# 0_3.net
KiCad netlist of a schematic drawn in Altium Designer
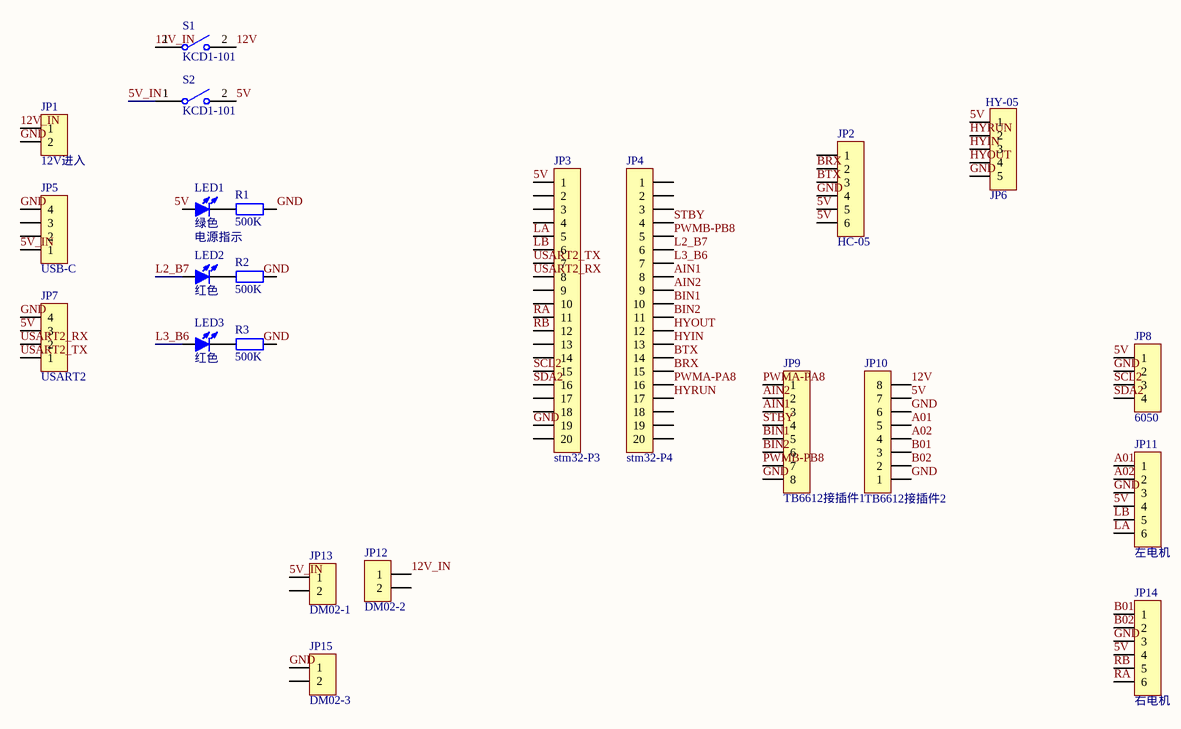
[diagram p0: 0.3.SchDoc]

(export (version "E")
  (design (tool "Eeschema 10.0.6"))
  (components
    (comp (ref "JP1")
      (value "HDR-1X2")
      (footprint "KF2EDGK5.08-LI-2P")
      (description "2P接插件")
      (fields (field (name "BOM名称") "12V进入") (field (name "版权归属") "源创客"))
      (libsource (lib "5.8 - 接插件-脚距5.08 (200mil) ") (part "Header 2"))
    )
    (comp (ref "JP2")
      (value "HC-05")
      (footprint "HDR2.54-M-LI-6P")
      (description "6P接插件")
      (fields (field (name "BOM名称") "HC-05") (field (name "版权归属") "封装库来自淘宝 ID：黄晶宝石"))
      (libsource (lib "5.3 - 接插件-脚距2.54 (100mil) ") (part "Header 6"))
    )
    (comp (ref "JP3")
      (value "HDR-1X20")
      (footprint "HDR2.54-M-LI-20P")
      (description "20P接插件")
      (fields (field (name "BOM名称") "stm32-P3") (field (name "版权归属") "封装库来自淘宝 ID：黄晶宝石"))
      (libsource (lib "5.3 - 接插件-脚距2.54 (100mil) ") (part "Header 20"))
    )
    (comp (ref "JP4")
      (value "HDR-1X20")
      (footprint "HDR2.54-M-LI-20P")
      (description "20P接插件")
      (fields (field (name "BOM名称") "stm32-P4") (field (name "版权归属") "封装库来自淘宝 ID：黄晶宝石"))
      (libsource (lib "") (part "Header 20_1"))
    )
    (comp (ref "JP5")
      (value "HDR-1X4")
      (footprint "HDR2.54-M-LI-4P")
      (description "4P接插件")
      (fields (field (name "BOM名称") "USB-C") (field (name "版权归属") "封装库来自淘宝 ID：黄晶宝石"))
      (libsource (lib "5.3 - 接插件-脚距2.54 (100mil) ") (part "Header 4"))
    )
    (comp (ref "JP6")
      (value "HY-05")
      (footprint "HDR2.54-M-LI-5P")
      (description "5P接插件")
      (fields (field (name "版权归属") "封装库来自淘宝 ID：黄晶宝石"))
      (libsource (lib "5.3 - 接插件-脚距2.54 (100mil) ") (part "Header 5"))
    )
    (comp (ref "JP7")
      (value "HDR-1X4")
      (footprint "HDR2.54-M-LI-4P")
      (description "4P接插件")
      (fields (field (name "BOM名称") "USART2") (field (name "版权归属") "封装库来自淘宝 ID：黄晶宝石"))
      (libsource (lib "5.3 - 接插件-脚距2.54 (100mil) ") (part "Header 4"))
    )
    (comp (ref "JP8")
      (value "HDR-1X4")
      (footprint "HDR2.54-M-LI-4P")
      (description "4P接插件")
      (fields (field (name "BOM名称") "6050") (field (name "版权归属") "封装库来自淘宝 ID：黄晶宝石"))
      (libsource (lib "") (part "Header 4_1"))
    )
    (comp (ref "JP9")
      (value "HDR-1X8")
      (footprint "HDR2.54-M-LI-8P")
      (description "8P接插件")
      (fields (field (name "BOM名称") "TB6612接插件1") (field (name "版权归属") "封装库来自淘宝 ID：黄晶宝石"))
      (libsource (lib "5.3 - 接插件-脚距2.54 (100mil) ") (part "Header 8"))
    )
    (comp (ref "JP10")
      (value "HDR-1X8")
      (footprint "HDR2.54-M-LI-8P")
      (description "8P接插件")
      (fields (field (name "BOM名称") "TB6612接插件2") (field (name "版权归属") "封装库来自淘宝 ID：黄晶宝石"))
      (libsource (lib "") (part "Header 8_1"))
    )
    (comp (ref "JP11")
      (value "HDR-1X6")
      (footprint "KF128-5.08-6P")
      (description "6P接插件")
      (fields (field (name "BOM名称") "左电机") (field (name "版权归属") "源创客"))
      (libsource (lib "5.8 - 接插件-脚距5.08 (200mil) ") (part "Header 6"))
    )
    (comp (ref "JP12")
      (value "HDR-1X2")
      (footprint "HDR2.54-M-LI-2P")
      (description "2P接插件")
      (fields (field (name "BOM名称") "DM02-2") (field (name "版权归属") "封装库来自淘宝 ID：黄晶宝石"))
      (libsource (lib "") (part "Header 2_1"))
    )
    (comp (ref "JP13")
      (value "HDR-1X2")
      (footprint "HDR2.54-M-LI-2P")
      (description "2P接插件")
      (fields (field (name "BOM名称") "DM02-1") (field (name "版权归属") "封装库来自淘宝 ID：黄晶宝石"))
      (libsource (lib "5.3 - 接插件-脚距2.54 (100mil) ") (part "Header 2"))
    )
    (comp (ref "JP14")
      (value "HDR-1X6")
      (footprint "KF128-5.08-6P")
      (description "6P接插件")
      (fields (field (name "BOM名称") "右电机") (field (name "版权归属") "源创客"))
      (libsource (lib "5.8 - 接插件-脚距5.08 (200mil) ") (part "Header 6"))
    )
    (comp (ref "JP15")
      (value "HDR-1X2")
      (footprint "HDR2.54-M-LI-2P")
      (description "2P接插件")
      (fields (field (name "BOM名称") "DM02-3") (field (name "版权归属") "封装库来自淘宝 ID：黄晶宝石"))
      (libsource (lib "5.3 - 接插件-脚距2.54 (100mil) ") (part "Header 2"))
    )
    (comp (ref "LED1")
      (value "绿色")
      (footprint "LED 0805G")
      (description "贴片LED")
      (fields (field (name "BOM名称") "电源指示") (field (name "版权归属") "源创客"))
      (libsource (lib "LED") (part "LED-SMD"))
    )
    (comp (ref "LED2")
      (value "红色")
      (footprint "LED 0805G")
      (description "贴片LED")
      (fields (field (name "版权归属") "源创客"))
      (libsource (lib "LED") (part "LED-SMD"))
    )
    (comp (ref "LED3")
      (value "红色")
      (footprint "LED 0805G")
      (description "贴片LED")
      (fields (field (name "版权归属") "源创客"))
      (libsource (lib "LED") (part "LED-SMD"))
    )
    (comp (ref "R1")
      (value "500K")
      (footprint "R 0805_M")
      (description "贴片电阻")
      (fields (field (name "版权归属") "来自淘宝 ID：黄晶宝石"))
      (libsource (lib "0.1 - 电阻-电容-电感") (part "R"))
    )
    (comp (ref "R2")
      (value "500K")
      (footprint "R 0805_M")
      (description "贴片电阻")
      (fields (field (name "版权归属") "来自淘宝 ID：黄晶宝石"))
      (libsource (lib "0.1 - 电阻-电容-电感") (part "R"))
    )
    (comp (ref "R3")
      (value "500K")
      (footprint "R 0805_M")
      (description "贴片电阻")
      (fields (field (name "版权归属") "来自淘宝 ID：黄晶宝石"))
      (libsource (lib "0.1 - 电阻-电容-电感") (part "R"))
    )
    (comp (ref "S1")
      (value "KCD1-101")
      (footprint "KCD1-101")
      (description "1路单刀船型开关")
      (fields (field (name "版权归属") "封装库来自淘宝 ID：黄晶宝石"))
      (libsource (lib "0.7 - 常用按键-开关") (part "KCD1-101"))
    )
    (comp (ref "S2")
      (value "KCD1-101")
      (footprint "KCD1-101")
      (description "1路单刀船型开关")
      (fields (field (name "版权归属") "封装库来自淘宝 ID：黄晶宝石"))
      (libsource (lib "0.7 - 常用按键-开关") (part "KCD1-101"))
    )
  )
  (nets
    (net (code "1") (name "/5V") (class "Default")
      (node (ref "JP10") (pin "7") (pinfunction "7_7") (pintype "passive"))
      (node (ref "JP11") (pin "4") (pinfunction "4_4") (pintype "passive"))
      (node (ref "JP14") (pin "4") (pinfunction "4_4") (pintype "passive"))
      (node (ref "JP2") (pin "5") (pinfunction "5_5") (pintype "passive"))
      (node (ref "JP2") (pin "6") (pinfunction "6_6") (pintype "passive"))
      (node (ref "JP3") (pin "1") (pinfunction "1_1") (pintype "passive"))
      (node (ref "JP6") (pin "1") (pinfunction "1_1") (pintype "passive"))
      (node (ref "JP7") (pin "3") (pinfunction "3_3") (pintype "passive"))
      (node (ref "JP8") (pin "1") (pinfunction "1_1") (pintype "passive"))
      (node (ref "LED1") (pin "1") (pinfunction "A_1") (pintype "passive"))
      (node (ref "S2") (pin "2") (pinfunction "2_2") (pintype "passive"))
    )
    (net (code "2") (name "/5V_IN") (class "Default")
      (node (ref "JP13") (pin "1") (pinfunction "1_1") (pintype "passive"))
      (node (ref "JP5") (pin "1") (pinfunction "1_1") (pintype "passive"))
      (node (ref "S2") (pin "1") (pinfunction "1_1") (pintype "passive"))
    )
    (net (code "3") (name "/12V") (class "Default")
      (node (ref "JP10") (pin "8") (pinfunction "8_8") (pintype "passive"))
      (node (ref "S1") (pin "2") (pinfunction "2_2") (pintype "passive"))
    )
    (net (code "4") (name "/12V_IN") (class "Default")
      (node (ref "JP1") (pin "1") (pinfunction "1_1") (pintype "passive"))
      (node (ref "JP12") (pin "1") (pinfunction "1_1") (pintype "passive"))
      (node (ref "S1") (pin "1") (pinfunction "1_1") (pintype "passive"))
    )
    (net (code "5") (name "/A01") (class "Default")
      (node (ref "JP10") (pin "5") (pinfunction "5_5") (pintype "passive"))
      (node (ref "JP11") (pin "1") (pinfunction "1_1") (pintype "passive"))
    )
    (net (code "6") (name "/A02") (class "Default")
      (node (ref "JP10") (pin "4") (pinfunction "4_4") (pintype "passive"))
      (node (ref "JP11") (pin "2") (pinfunction "2_2") (pintype "passive"))
    )
    (net (code "7") (name "/AIN1") (class "Default")
      (node (ref "JP4") (pin "8") (pinfunction "8_8") (pintype "passive"))
      (node (ref "JP9") (pin "3") (pinfunction "3_3") (pintype "passive"))
    )
    (net (code "8") (name "/AIN2") (class "Default")
      (node (ref "JP4") (pin "9") (pinfunction "9_9") (pintype "passive"))
      (node (ref "JP9") (pin "2") (pinfunction "2_2") (pintype "passive"))
    )
    (net (code "9") (name "/B01") (class "Default")
      (node (ref "JP10") (pin "3") (pinfunction "3_3") (pintype "passive"))
      (node (ref "JP14") (pin "1") (pinfunction "1_1") (pintype "passive"))
    )
    (net (code "10") (name "/B02") (class "Default")
      (node (ref "JP10") (pin "2") (pinfunction "2_2") (pintype "passive"))
      (node (ref "JP14") (pin "2") (pinfunction "2_2") (pintype "passive"))
    )
    (net (code "11") (name "/BIN1") (class "Default")
      (node (ref "JP4") (pin "10") (pinfunction "10_10") (pintype "passive"))
      (node (ref "JP9") (pin "5") (pinfunction "5_5") (pintype "passive"))
    )
    (net (code "12") (name "/BIN2") (class "Default")
      (node (ref "JP4") (pin "11") (pinfunction "11_11") (pintype "passive"))
      (node (ref "JP9") (pin "6") (pinfunction "6_6") (pintype "passive"))
    )
    (net (code "13") (name "/BRX") (class "Default")
      (node (ref "JP2") (pin "2") (pinfunction "2_2") (pintype "passive"))
      (node (ref "JP4") (pin "15") (pinfunction "15_15") (pintype "passive"))
    )
    (net (code "14") (name "/BTX") (class "Default")
      (node (ref "JP2") (pin "3") (pinfunction "3_3") (pintype "passive"))
      (node (ref "JP4") (pin "14") (pinfunction "14_14") (pintype "passive"))
    )
    (net (code "15") (name "/GND") (class "Default")
      (node (ref "JP1") (pin "2") (pinfunction "2_2") (pintype "passive"))
      (node (ref "JP10") (pin "1") (pinfunction "1_1") (pintype "passive"))
      (node (ref "JP10") (pin "6") (pinfunction "6_6") (pintype "passive"))
      (node (ref "JP11") (pin "3") (pinfunction "3_3") (pintype "passive"))
      (node (ref "JP14") (pin "3") (pinfunction "3_3") (pintype "passive"))
      (node (ref "JP15") (pin "1") (pinfunction "1_1") (pintype "passive"))
      (node (ref "JP2") (pin "4") (pinfunction "4_4") (pintype "passive"))
      (node (ref "JP3") (pin "19") (pinfunction "19_19") (pintype "passive"))
      (node (ref "JP5") (pin "4") (pinfunction "4_4") (pintype "passive"))
      (node (ref "JP6") (pin "5") (pinfunction "5_5") (pintype "passive"))
      (node (ref "JP7") (pin "4") (pinfunction "4_4") (pintype "passive"))
      (node (ref "JP8") (pin "2") (pinfunction "2_2") (pintype "passive"))
      (node (ref "JP9") (pin "8") (pinfunction "8_8") (pintype "passive"))
      (node (ref "R1") (pin "2") (pinfunction "2_2") (pintype "passive"))
      (node (ref "R2") (pin "2") (pinfunction "2_2") (pintype "passive"))
      (node (ref "R3") (pin "2") (pinfunction "2_2") (pintype "passive"))
    )
    (net (code "16") (name "/HYIN") (class "Default")
      (node (ref "JP4") (pin "13") (pinfunction "13_13") (pintype "passive"))
      (node (ref "JP6") (pin "3") (pinfunction "3_3") (pintype "passive"))
    )
    (net (code "17") (name "/HYOUT") (class "Default")
      (node (ref "JP4") (pin "12") (pinfunction "12_12") (pintype "passive"))
      (node (ref "JP6") (pin "4") (pinfunction "4_4") (pintype "passive"))
    )
    (net (code "18") (name "/HYRUN") (class "Default")
      (node (ref "JP4") (pin "17") (pinfunction "17_17") (pintype "passive"))
      (node (ref "JP6") (pin "2") (pinfunction "2_2") (pintype "passive"))
    )
    (net (code "19") (name "/L2_B7") (class "Default")
      (node (ref "JP4") (pin "6") (pinfunction "6_6") (pintype "passive"))
      (node (ref "LED2") (pin "1") (pinfunction "A_1") (pintype "passive"))
    )
    (net (code "20") (name "/L3_B6") (class "Default")
      (node (ref "JP4") (pin "7") (pinfunction "7_7") (pintype "passive"))
      (node (ref "LED3") (pin "1") (pinfunction "A_1") (pintype "passive"))
    )
    (net (code "21") (name "/LA") (class "Default")
      (node (ref "JP11") (pin "6") (pinfunction "6_6") (pintype "passive"))
      (node (ref "JP3") (pin "5") (pinfunction "5_5") (pintype "passive"))
    )
    (net (code "22") (name "/LB") (class "Default")
      (node (ref "JP11") (pin "5") (pinfunction "5_5") (pintype "passive"))
      (node (ref "JP3") (pin "6") (pinfunction "6_6") (pintype "passive"))
    )
    (net (code "23") (name "/PWMA-PA8") (class "Default")
      (node (ref "JP4") (pin "16") (pinfunction "16_16") (pintype "passive"))
      (node (ref "JP9") (pin "1") (pinfunction "1_1") (pintype "passive"))
    )
    (net (code "24") (name "/PWMB-PB8") (class "Default")
      (node (ref "JP4") (pin "5") (pinfunction "5_5") (pintype "passive"))
      (node (ref "JP9") (pin "7") (pinfunction "7_7") (pintype "passive"))
    )
    (net (code "25") (name "/RA") (class "Default")
      (node (ref "JP14") (pin "6") (pinfunction "6_6") (pintype "passive"))
      (node (ref "JP3") (pin "11") (pinfunction "11_11") (pintype "passive"))
    )
    (net (code "26") (name "/RB") (class "Default")
      (node (ref "JP14") (pin "5") (pinfunction "5_5") (pintype "passive"))
      (node (ref "JP3") (pin "12") (pinfunction "12_12") (pintype "passive"))
    )
    (net (code "27") (name "/SCL2") (class "Default")
      (node (ref "JP3") (pin "15") (pinfunction "15_15") (pintype "passive"))
      (node (ref "JP8") (pin "3") (pinfunction "3_3") (pintype "passive"))
    )
    (net (code "28") (name "/SDA2") (class "Default")
      (node (ref "JP3") (pin "16") (pinfunction "16_16") (pintype "passive"))
      (node (ref "JP8") (pin "4") (pinfunction "4_4") (pintype "passive"))
    )
    (net (code "29") (name "/STBY") (class "Default")
      (node (ref "JP4") (pin "4") (pinfunction "4_4") (pintype "passive"))
      (node (ref "JP9") (pin "4") (pinfunction "4_4") (pintype "passive"))
    )
    (net (code "30") (name "/USART2_RX") (class "Default")
      (node (ref "JP3") (pin "8") (pinfunction "8_8") (pintype "passive"))
      (node (ref "JP7") (pin "2") (pinfunction "2_2") (pintype "passive"))
    )
    (net (code "31") (name "/USART2_TX") (class "Default")
      (node (ref "JP3") (pin "7") (pinfunction "7_7") (pintype "passive"))
      (node (ref "JP7") (pin "1") (pinfunction "1_1") (pintype "passive"))
    )
    (net (code "32") (name "Net-(LED1-K)") (class "Default")
      (node (ref "LED1") (pin "2") (pinfunction "K_2") (pintype "passive"))
      (node (ref "R1") (pin "1") (pinfunction "1_1") (pintype "passive"))
    )
    (net (code "33") (name "Net-(LED2-K)") (class "Default")
      (node (ref "LED2") (pin "2") (pinfunction "K_2") (pintype "passive"))
      (node (ref "R2") (pin "1") (pinfunction "1_1") (pintype "passive"))
    )
    (net (code "34") (name "Net-(LED3-K)") (class "Default")
      (node (ref "LED3") (pin "2") (pinfunction "K_2") (pintype "passive"))
      (node (ref "R3") (pin "1") (pinfunction "1_1") (pintype "passive"))
    )
    (net (code "35") (name "unconnected-(JP2-Pad1)") (class "Default")
      (node (ref "JP2") (pin "1") (pinfunction "1_1") (pintype "passive"))
    )
    (net (code "36") (name "unconnected-(JP3-Pad2)") (class "Default")
      (node (ref "JP3") (pin "2") (pinfunction "2_2") (pintype "passive"))
    )
    (net (code "37") (name "unconnected-(JP3-Pad3)") (class "Default")
      (node (ref "JP3") (pin "3") (pinfunction "3_3") (pintype "passive"))
    )
    (net (code "38") (name "unconnected-(JP3-Pad4)") (class "Default")
      (node (ref "JP3") (pin "4") (pinfunction "4_4") (pintype "passive"))
    )
    (net (code "39") (name "unconnected-(JP3-Pad9)") (class "Default")
      (node (ref "JP3") (pin "9") (pinfunction "9_9") (pintype "passive"))
    )
    (net (code "40") (name "unconnected-(JP3-Pad10)") (class "Default")
      (node (ref "JP3") (pin "10") (pinfunction "10_10") (pintype "passive"))
    )
    (net (code "41") (name "unconnected-(JP3-Pad13)") (class "Default")
      (node (ref "JP3") (pin "13") (pinfunction "13_13") (pintype "passive"))
    )
    (net (code "42") (name "unconnected-(JP3-Pad14)") (class "Default")
      (node (ref "JP3") (pin "14") (pinfunction "14_14") (pintype "passive"))
    )
    (net (code "43") (name "unconnected-(JP3-Pad17)") (class "Default")
      (node (ref "JP3") (pin "17") (pinfunction "17_17") (pintype "passive"))
    )
    (net (code "44") (name "unconnected-(JP3-Pad18)") (class "Default")
      (node (ref "JP3") (pin "18") (pinfunction "18_18") (pintype "passive"))
    )
    (net (code "45") (name "unconnected-(JP3-Pad20)") (class "Default")
      (node (ref "JP3") (pin "20") (pinfunction "20_20") (pintype "passive"))
    )
    (net (code "46") (name "unconnected-(JP4-Pad1)") (class "Default")
      (node (ref "JP4") (pin "1") (pinfunction "1_1") (pintype "passive"))
    )
    (net (code "47") (name "unconnected-(JP4-Pad2)") (class "Default")
      (node (ref "JP4") (pin "2") (pinfunction "2_2") (pintype "passive"))
    )
    (net (code "48") (name "unconnected-(JP4-Pad3)") (class "Default")
      (node (ref "JP4") (pin "3") (pinfunction "3_3") (pintype "passive"))
    )
    (net (code "49") (name "unconnected-(JP4-Pad18)") (class "Default")
      (node (ref "JP4") (pin "18") (pinfunction "18_18") (pintype "passive"))
    )
    (net (code "50") (name "unconnected-(JP4-Pad19)") (class "Default")
      (node (ref "JP4") (pin "19") (pinfunction "19_19") (pintype "passive"))
    )
    (net (code "51") (name "unconnected-(JP4-Pad20)") (class "Default")
      (node (ref "JP4") (pin "20") (pinfunction "20_20") (pintype "passive"))
    )
    (net (code "52") (name "unconnected-(JP5-Pad2)") (class "Default")
      (node (ref "JP5") (pin "2") (pinfunction "2_2") (pintype "passive"))
    )
    (net (code "53") (name "unconnected-(JP5-Pad3)") (class "Default")
      (node (ref "JP5") (pin "3") (pinfunction "3_3") (pintype "passive"))
    )
    (net (code "54") (name "unconnected-(JP12-Pad2)") (class "Default")
      (node (ref "JP12") (pin "2") (pinfunction "2_2") (pintype "passive"))
    )
    (net (code "55") (name "unconnected-(JP13-Pad2)") (class "Default")
      (node (ref "JP13") (pin "2") (pinfunction "2_2") (pintype "passive"))
    )
    (net (code "56") (name "unconnected-(JP15-Pad2)") (class "Default")
      (node (ref "JP15") (pin "2") (pinfunction "2_2") (pintype "passive"))
    )
  )
)
